# 4_Display_NFC.net
KiCad netlist of a schematic drawn in Altium Designer
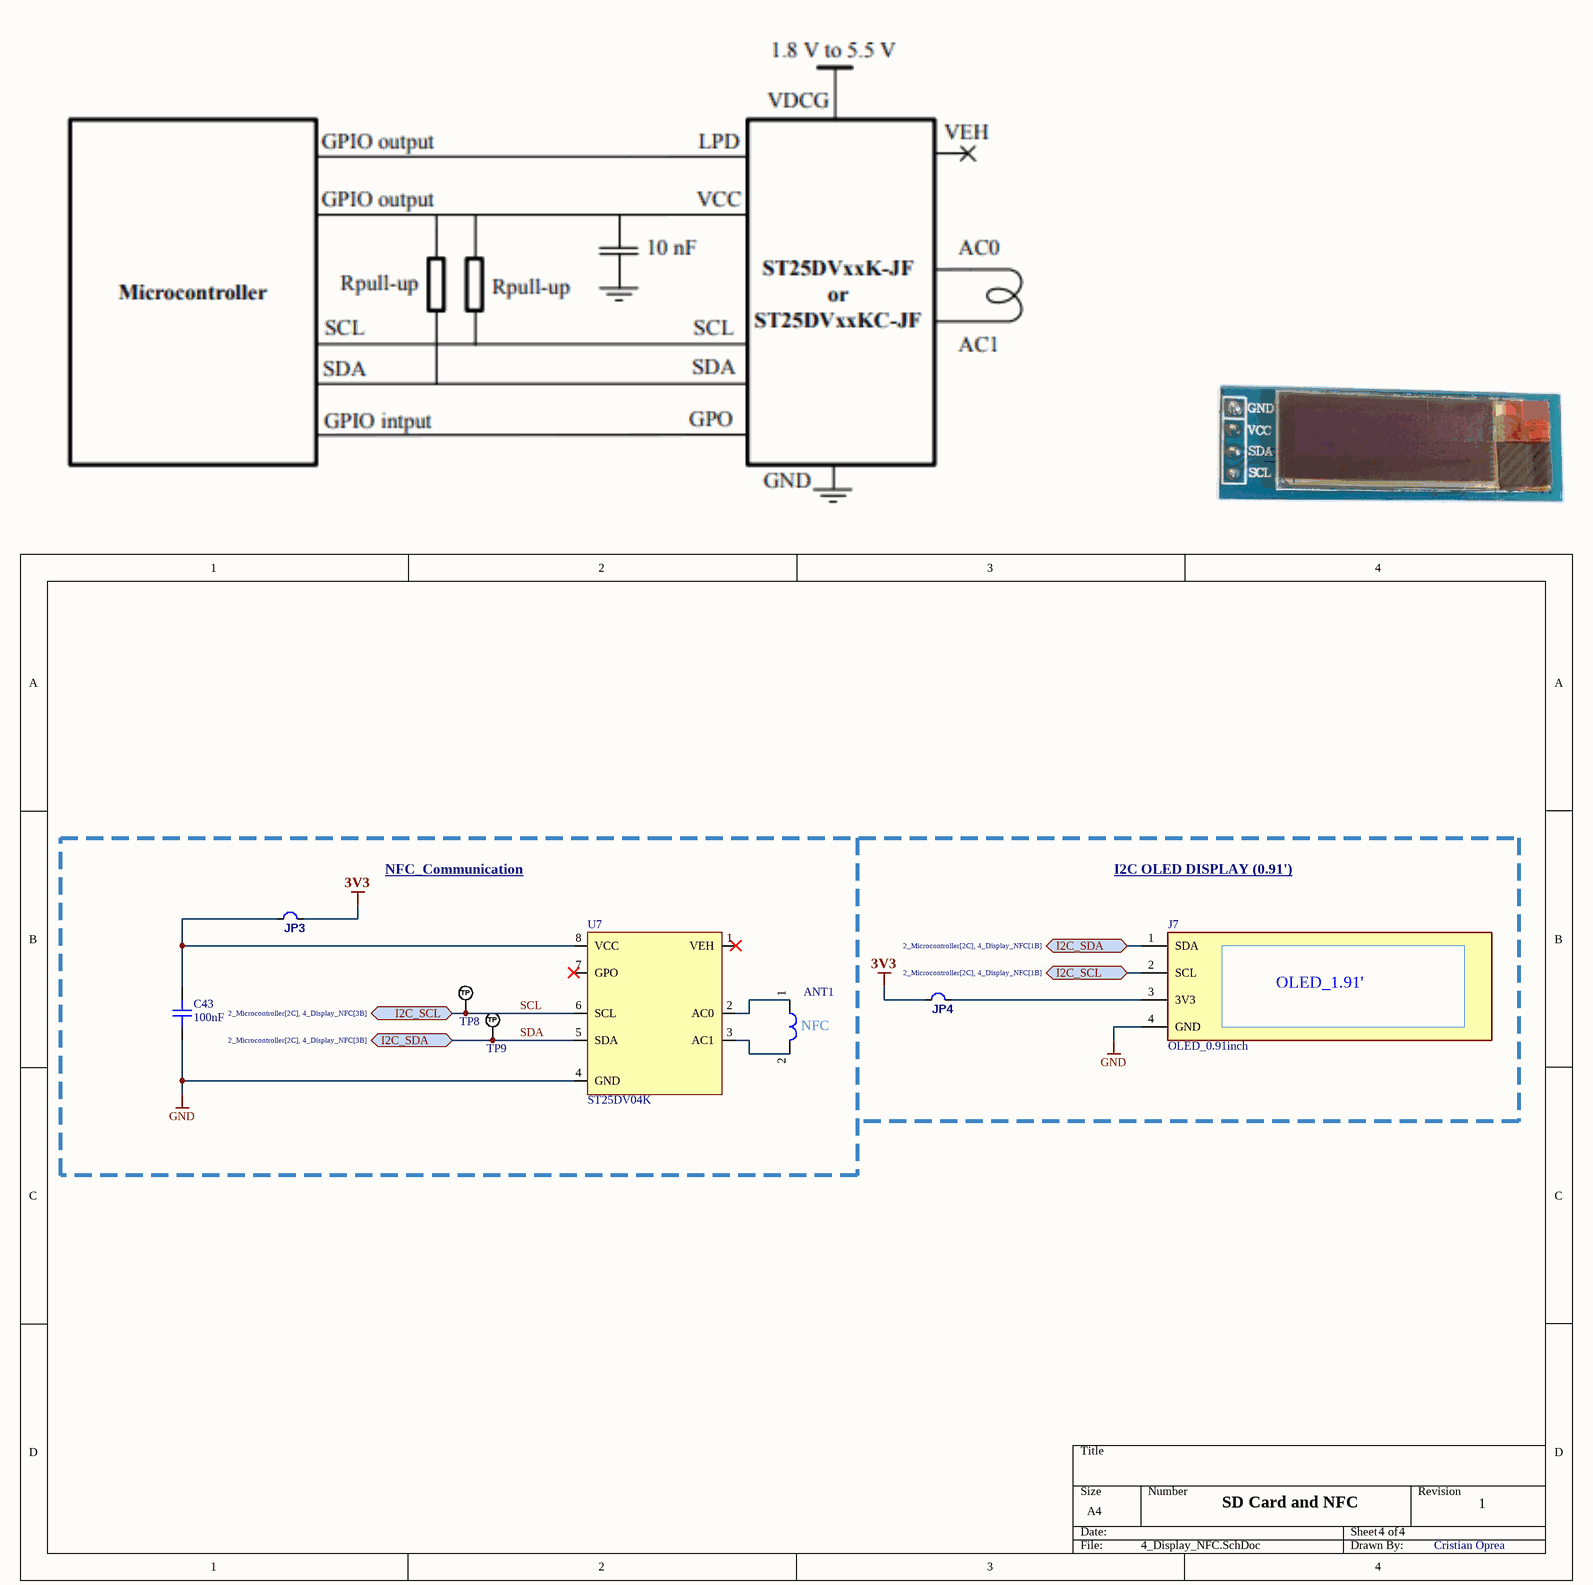
[diagram p0: 4_Display_NFC.SchDoc]

(export (version "E")
  (design (tool "Eeschema 10.0.6"))
  (components
    (comp (ref "ANT1")
      (value "NFC_ANTENNA")
      (footprint "ANT16")
      (libsource (lib "Schlib1") (part "NFC_ANTENNA"))
    )
    (comp (ref "C43")
      (value "100nF")
      (footprint "C0603")
      (description "Capacitor SMD 0603")
      (libsource (lib "Schlib1") (part "CAP_0603"))
    )
    (comp (ref "J7")
      (value "OLED_0.91inch")
      (footprint "OLED_0.91in")
      (description "I2C OLED display (horizontal) 0.91inch")
      (libsource (lib "Schlib1") (part "OLED_0.91inch"))
    )
    (comp (ref "JP3")
      (value "JUMPER")
      (footprint "HEADER_1x2_2.54")
      (libsource (lib "Schlib1") (part "JUMPER"))
    )
    (comp (ref "JP4")
      (value "JUMPER")
      (footprint "HEADER_1x2_2.54")
      (libsource (lib "Schlib1") (part "JUMPER"))
    )
    (comp (ref "TP8")
      (value "TP_NOBOM")
      (footprint "TEST_PAD_THD")
      (description "Test Point Round 1mm (NO BOM)")
      (libsource (lib "Schlib_H2") (part "TEST_POINT_RND_1MM"))
    )
    (comp (ref "TP9")
      (value "TP_NOBOM")
      (footprint "TEST_PAD_THD")
      (description "Test Point Round 1mm (NO BOM)")
      (libsource (lib "Schlib_H2") (part "TEST_POINT_RND_1MM"))
    )
    (comp (ref "U7")
      (value "ST25DV04K")
      (footprint "SOIC-SN8_N")
      (description "ST25DO4K NFC module with I2C")
      (libsource (lib "Schlib1") (part "ST25DV04K"))
    )
  )
  (nets
    (net (code "1") (name "/SCL") (class "Default")
      (node (ref "J7") (pin "2") (pinfunction "SCL_2") (pintype "passive"))
      (node (ref "TP8") (pin "1") (pinfunction "TP_1") (pintype "passive"))
      (node (ref "U7") (pin "6") (pinfunction "SCL_6") (pintype "passive"))
    )
    (net (code "2") (name "/SDA") (class "Default")
      (node (ref "J7") (pin "1") (pinfunction "SDA_1") (pintype "passive"))
      (node (ref "TP9") (pin "1") (pinfunction "TP_1") (pintype "passive"))
      (node (ref "U7") (pin "5") (pinfunction "SDA_5") (pintype "passive"))
    )
    (net (code "3") (name "3V3") (class "Default")
      (node (ref "JP3") (pin "2") (pinfunction "2_2") (pintype "passive"))
      (node (ref "JP4") (pin "1") (pinfunction "1_1") (pintype "passive"))
    )
    (net (code "4") (name "GND") (class "Default")
      (node (ref "C43") (pin "1") (pinfunction "1_1") (pintype "passive"))
      (node (ref "J7") (pin "4") (pinfunction "GND_4") (pintype "passive"))
      (node (ref "U7") (pin "4") (pinfunction "GND_4") (pintype "passive"))
    )
    (net (code "5") (name "Net-(J7-3V3)") (class "Default")
      (node (ref "J7") (pin "3") (pinfunction "3V3_3") (pintype "passive"))
      (node (ref "JP4") (pin "2") (pinfunction "2_2") (pintype "passive"))
    )
    (net (code "6") (name "Net-(U7-AC0)") (class "Default")
      (node (ref "ANT1") (pin "1") (pinfunction "1_1") (pintype "passive"))
      (node (ref "U7") (pin "2") (pinfunction "AC0_2") (pintype "passive"))
    )
    (net (code "7") (name "Net-(U7-AC1)") (class "Default")
      (node (ref "ANT1") (pin "2") (pinfunction "2_2") (pintype "passive"))
      (node (ref "U7") (pin "3") (pinfunction "AC1_3") (pintype "passive"))
    )
    (net (code "8") (name "Net-(U7-VCC)") (class "Default")
      (node (ref "C43") (pin "2") (pinfunction "2_2") (pintype "passive"))
      (node (ref "JP3") (pin "1") (pinfunction "1_1") (pintype "passive"))
      (node (ref "U7") (pin "8") (pinfunction "VCC_8") (pintype "passive"))
    )
    (net (code "9") (name "unconnected-(U7-GPO-Pad7)") (class "Default")
      (node (ref "U7") (pin "7") (pinfunction "GPO_7") (pintype "passive+no_connect"))
    )
    (net (code "10") (name "unconnected-(U7-VEH-Pad1)") (class "Default")
      (node (ref "U7") (pin "1") (pinfunction "VEH_1") (pintype "passive+no_connect"))
    )
  )
)
